# RS3232.net
KiCad netlist of a schematic drawn in Altium Designer
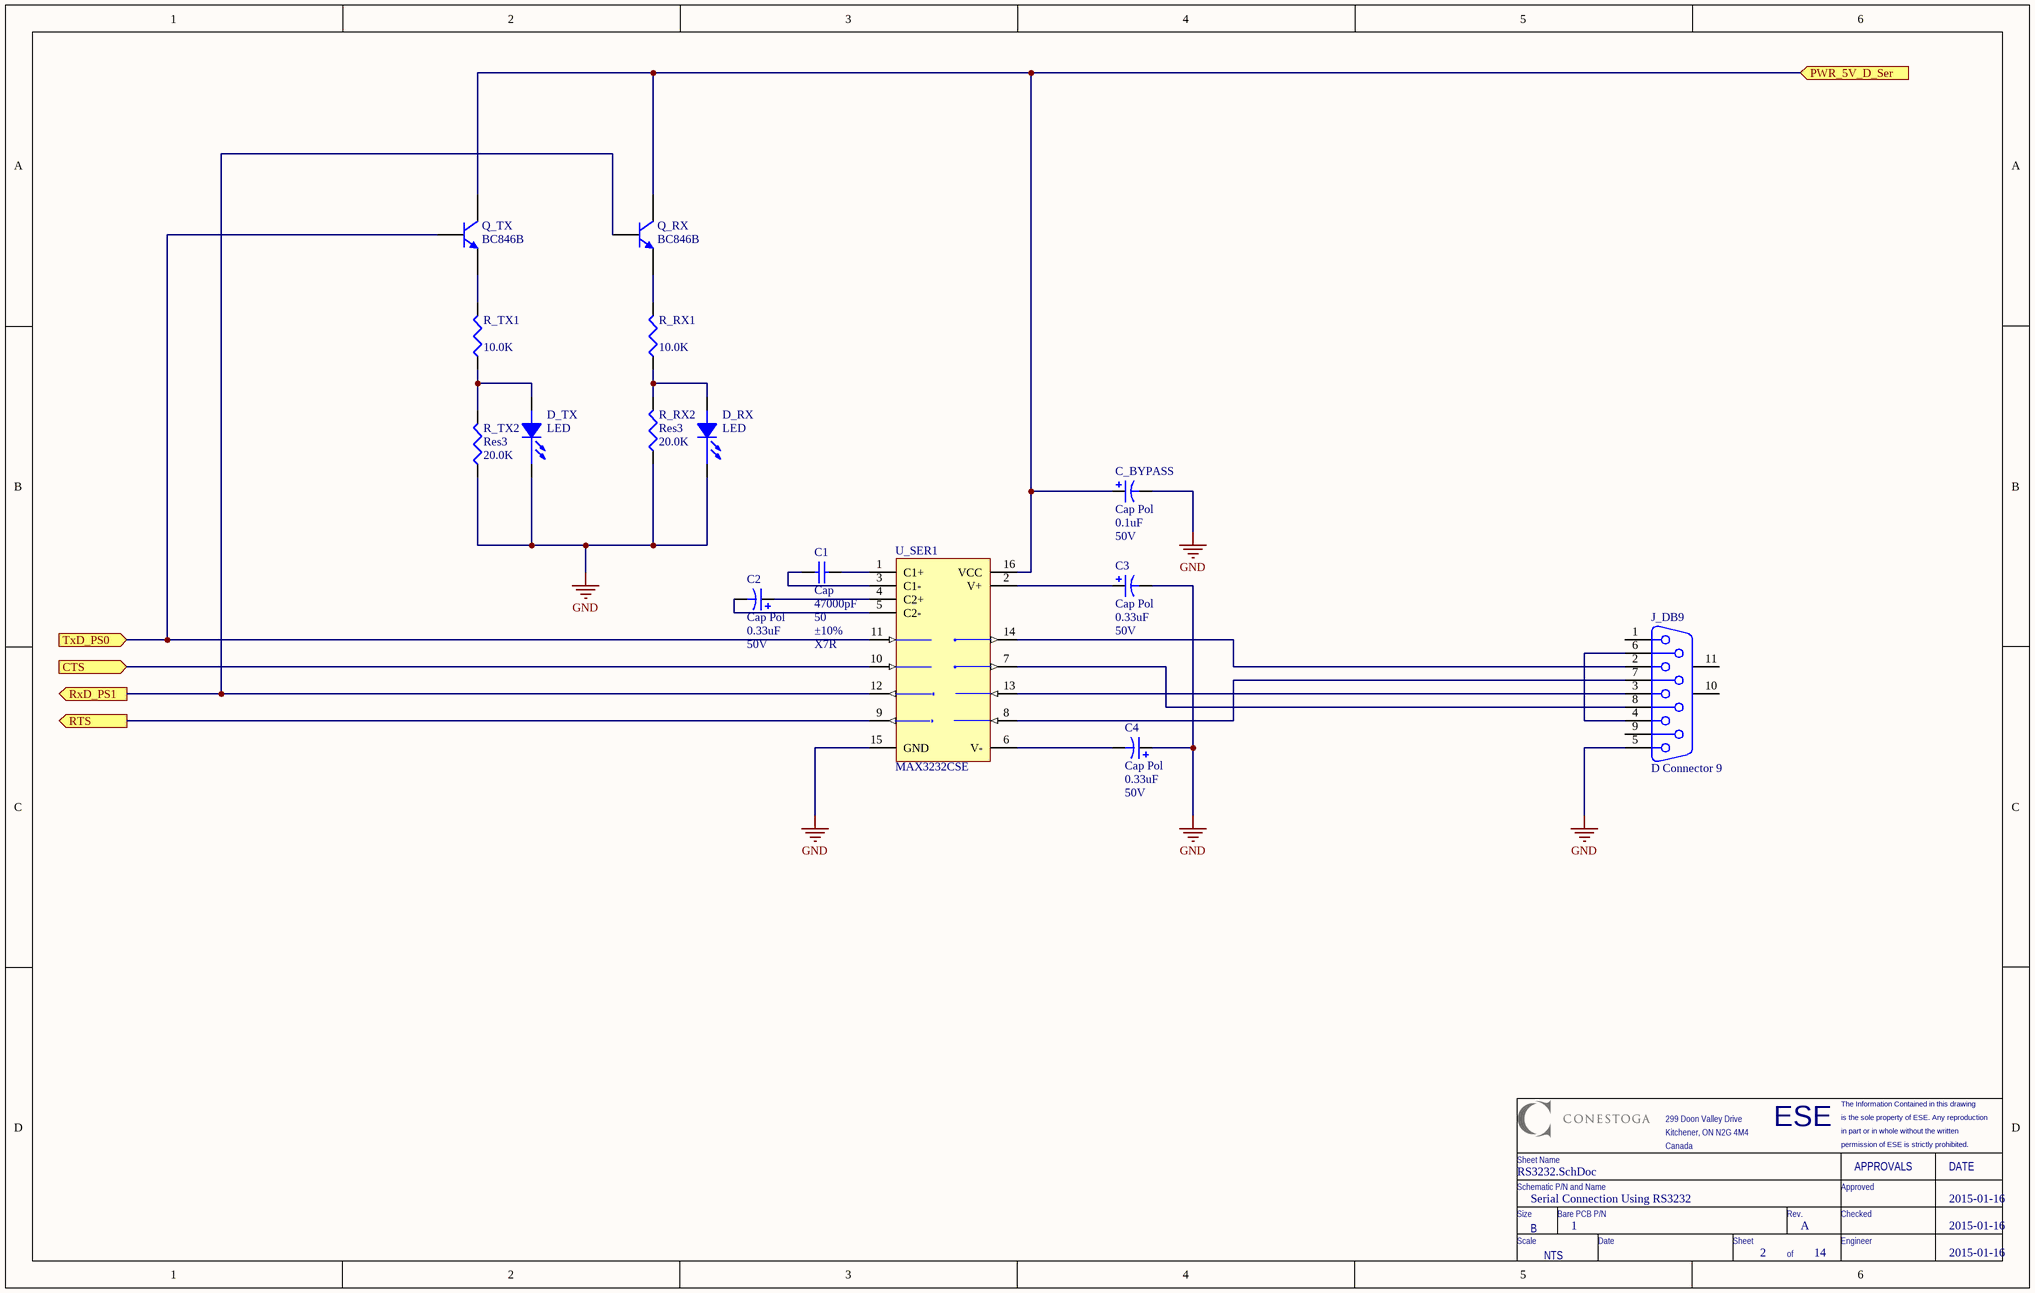
[diagram p0: RS3232.SchDoc]

(export (version "E")
  (design (tool "Eeschema 10.0.6"))
  (components
    (comp (ref "C1")
      (value "Cap")
      (footprint "CAPC2012X09M")
      (description "CAP CER 47000pF 50v X7R 0805")
      (fields
        (field (name "ALTIUM_VALUE") "47000pF")
        (field (name "WV") "50")
        (field (name "TOLERANCE") "±10%")
        (field (name "TYPE") "X7R")
        (field (name "MPN") "C0805C473K5RACTU")
      )
      (libsource (lib "esd_library") (part "CAP-X7R-47000pF-50V-±10%"))
    )
    (comp (ref "C2")
      (value "Cap Pol")
      (footprint "CAPACITOR_3MM")
      (description "CAP 85C 0.33uF ±20% 50V WX Series Aluminum Electrolytic")
      (fields
        (field (name "MPN") "UWX1HR33MCL2GB")
        (field (name "ALTIUM_VALUE") "0.33uF")
        (field (name "VOLTAGE") "50V")
      )
      (libsource (lib "esd_library") (part "Cap Polar-0.33uF-50V"))
    )
    (comp (ref "C3")
      (value "Cap Pol")
      (footprint "CAPACITOR_3MM")
      (description "CAP 85C 0.33uF ±20% 50V WX Series Aluminum Electrolytic")
      (fields
        (field (name "MPN") "UWX1HR33MCL2GB")
        (field (name "ALTIUM_VALUE") "0.33uF")
        (field (name "VOLTAGE") "50V")
      )
      (libsource (lib "esd_library") (part "Cap Polar-0.33uF-50V"))
    )
    (comp (ref "C4")
      (value "Cap Pol")
      (footprint "CAPACITOR_3MM")
      (description "CAP 85C 0.33uF ±20% 50V WX Series Aluminum Electrolytic")
      (fields
        (field (name "MPN") "UWX1HR33MCL2GB")
        (field (name "ALTIUM_VALUE") "0.33uF")
        (field (name "VOLTAGE") "50V")
      )
      (libsource (lib "esd_library") (part "Cap Polar-0.33uF-50V"))
    )
    (comp (ref "C_BYPASS")
      (value "Cap Pol")
      (footprint "CAPACITOR_3MM")
      (description "CAP 85C 0.1uF ±20% 50V WX Series Aluminum Electrolytic")
      (fields
        (field (name "MPN") "UWX1H0R1MCL2GB")
        (field (name "ALTIUM_VALUE") "0.1uF")
        (field (name "VOLTAGE") "50V")
      )
      (libsource (lib "esd_library") (part "Cap Polar-0.1uF-50V"))
    )
    (comp (ref "D_RX") (value "LED") (footprint "0603") (libsource (lib "esd_library") (part "LED")))
    (comp (ref "D_TX") (value "LED") (footprint "0603") (libsource (lib "esd_library") (part "LED")))
    (comp (ref "J_DB9")
      (value "D Connector 9")
      (footprint "DSUB1.385-2H9")
      (description "Receptacle Assembly, 9 Position, Right Angle")
      (fields (field (name "MPN") "ADF09A-KG-TASB3-R"))
      (libsource (lib "esd_library") (part "D Connector 9"))
    )
    (comp (ref "Q_RX")
      (value "BC846B")
      (footprint "SOT95P230X110-3M")
      (description "NPN General Purpose Amplifier")
      (libsource (lib "esd_library") (part "BC846B"))
    )
    (comp (ref "Q_TX")
      (value "BC846B")
      (footprint "SOT95P230X110-3M")
      (description "NPN General Purpose Amplifier")
      (libsource (lib "esd_library") (part "BC846B"))
    )
    (comp (ref "R_RX1")
      (value "10.0K")
      (footprint "RESC2112X05M")
      (description "RES SMD 10.0K OHM 1% 1/8W 0805")
      (fields (field (name "MPN") "CRCW080510K0FKEA") (field (name "Comment") "Res3"))
      (libsource (lib "esd_library") (part "Resistor_10.0K"))
    )
    (comp (ref "R_RX2")
      (value "Res3")
      (footprint "RESC2112X05M")
      (description "RES SMD 20.0K OHM 1% 1/8W 0805")
      (fields (field (name "ALTIUM_VALUE") "20.0K") (field (name "MPN") "CRCW080520K0FKEA"))
      (libsource (lib "esd_library") (part "Resistor_20.0K"))
    )
    (comp (ref "R_TX1")
      (value "10.0K")
      (footprint "RESC2112X05M")
      (description "RES SMD 10.0K OHM 1% 1/8W 0805")
      (fields (field (name "MPN") "CRCW080510K0FKEA") (field (name "Comment") "Res3"))
      (libsource (lib "esd_library") (part "Resistor_10.0K"))
    )
    (comp (ref "R_TX2")
      (value "Res3")
      (footprint "RESC2112X05M")
      (description "RES SMD 20.0K OHM 1% 1/8W 0805")
      (fields (field (name "ALTIUM_VALUE") "20.0K") (field (name "MPN") "CRCW080520K0FKEA"))
      (libsource (lib "esd_library") (part "Resistor_20.0K"))
    )
    (comp (ref "U_SER1")
      (value "MAX3232CSE")
      (footprint "NSO16_N")
      (description "3.0V TO 5.5V, Low-Power, up to 1Mbps, True RS-232 Transceiver Using Four 0.1µF External Capacitor")
      (fields (field (name "MPN") "MAX3232CSE+") (field (name "PUBLISHER") "Altium Limited"))
      (libsource (lib "esd_library") (part "MAX3232CSE"))
    )
  )
  (nets
    (net (code "1") (name "/CTS") (class "Default")
      (node (ref "U_SER1") (pin "10") (pinfunction "T2IN_10") (pintype "input"))
    )
    (net (code "2") (name "/PWR_5V_D_Ser") (class "Default")
      (node (ref "C_BYPASS") (pin "1") (pinfunction "1_1") (pintype "passive"))
      (node (ref "Q_RX") (pin "3") (pinfunction "C_3") (pintype "passive"))
      (node (ref "Q_TX") (pin "3") (pinfunction "C_3") (pintype "passive"))
      (node (ref "U_SER1") (pin "16") (pinfunction "VCC_16") (pintype "power_in"))
    )
    (net (code "3") (name "/RTS") (class "Default")
      (node (ref "U_SER1") (pin "9") (pinfunction "R2OUT_9") (pintype "output"))
    )
    (net (code "4") (name "/RxD_PS1") (class "Default")
      (node (ref "Q_RX") (pin "1") (pinfunction "B_1") (pintype "passive"))
      (node (ref "U_SER1") (pin "12") (pinfunction "R1OUT_12") (pintype "output"))
    )
    (net (code "5") (name "/TxD_PS0") (class "Default")
      (node (ref "Q_TX") (pin "1") (pinfunction "B_1") (pintype "passive"))
      (node (ref "U_SER1") (pin "11") (pinfunction "T1IN_11") (pintype "input"))
    )
    (net (code "6") (name "GND") (class "Default")
      (node (ref "C3") (pin "2") (pinfunction "2_2") (pintype "passive"))
      (node (ref "C4") (pin "1") (pinfunction "1_1") (pintype "passive"))
      (node (ref "C_BYPASS") (pin "2") (pinfunction "2_2") (pintype "passive"))
      (node (ref "D_RX") (pin "2") (pinfunction "C_2") (pintype "passive"))
      (node (ref "D_TX") (pin "2") (pinfunction "C_2") (pintype "passive"))
      (node (ref "J_DB9") (pin "5") (pinfunction "5_5") (pintype "passive"))
      (node (ref "R_RX2") (pin "1") (pinfunction "1_1") (pintype "passive"))
      (node (ref "R_TX2") (pin "1") (pinfunction "1_1") (pintype "passive"))
      (node (ref "U_SER1") (pin "15") (pinfunction "GND_15") (pintype "power_in"))
    )
    (net (code "7") (name "Net-(D_RX-A)") (class "Default")
      (node (ref "D_RX") (pin "1") (pinfunction "A_1") (pintype "passive"))
      (node (ref "R_RX1") (pin "1") (pinfunction "1_1") (pintype "passive"))
      (node (ref "R_RX2") (pin "2") (pinfunction "2_2") (pintype "passive"))
    )
    (net (code "8") (name "Net-(D_TX-A)") (class "Default")
      (node (ref "D_TX") (pin "1") (pinfunction "A_1") (pintype "passive"))
      (node (ref "R_TX1") (pin "1") (pinfunction "1_1") (pintype "passive"))
      (node (ref "R_TX2") (pin "2") (pinfunction "2_2") (pintype "passive"))
    )
    (net (code "9") (name "Net-(J_DB9-Pad4)") (class "Default")
      (node (ref "J_DB9") (pin "4") (pinfunction "4_4") (pintype "passive"))
      (node (ref "J_DB9") (pin "6") (pinfunction "6_6") (pintype "passive"))
    )
    (net (code "10") (name "Net-(Q_RX-E)") (class "Default")
      (node (ref "Q_RX") (pin "2") (pinfunction "E_2") (pintype "passive"))
      (node (ref "R_RX1") (pin "2") (pinfunction "2_2") (pintype "passive"))
    )
    (net (code "11") (name "Net-(Q_TX-E)") (class "Default")
      (node (ref "Q_TX") (pin "2") (pinfunction "E_2") (pintype "passive"))
      (node (ref "R_TX1") (pin "2") (pinfunction "2_2") (pintype "passive"))
    )
    (net (code "12") (name "Net-(U_SER1-C1+)") (class "Default")
      (node (ref "C1") (pin "2") (pinfunction "2_2") (pintype "passive"))
      (node (ref "U_SER1") (pin "1") (pinfunction "C1+_1") (pintype "passive"))
    )
    (net (code "13") (name "Net-(U_SER1-C1-)") (class "Default")
      (node (ref "C1") (pin "1") (pinfunction "1_1") (pintype "passive"))
      (node (ref "U_SER1") (pin "3") (pinfunction "C1-_3") (pintype "passive"))
    )
    (net (code "14") (name "Net-(U_SER1-C2+)") (class "Default")
      (node (ref "C2") (pin "1") (pinfunction "1_1") (pintype "passive"))
      (node (ref "U_SER1") (pin "4") (pinfunction "C2+_4") (pintype "passive"))
    )
    (net (code "15") (name "Net-(U_SER1-C2-)") (class "Default")
      (node (ref "C2") (pin "2") (pinfunction "2_2") (pintype "passive"))
      (node (ref "U_SER1") (pin "5") (pinfunction "C2-_5") (pintype "passive"))
    )
    (net (code "16") (name "Net-(U_SER1-R1IN)") (class "Default")
      (node (ref "J_DB9") (pin "3") (pinfunction "3_3") (pintype "passive"))
      (node (ref "U_SER1") (pin "13") (pinfunction "R1IN_13") (pintype "input"))
    )
    (net (code "17") (name "Net-(U_SER1-R2IN)") (class "Default")
      (node (ref "J_DB9") (pin "7") (pinfunction "7_7") (pintype "passive"))
      (node (ref "U_SER1") (pin "8") (pinfunction "R2IN_8") (pintype "input"))
    )
    (net (code "18") (name "Net-(U_SER1-T1OUT)") (class "Default")
      (node (ref "J_DB9") (pin "2") (pinfunction "2_2") (pintype "passive"))
      (node (ref "U_SER1") (pin "14") (pinfunction "T1OUT_14") (pintype "output"))
    )
    (net (code "19") (name "Net-(U_SER1-T2OUT)") (class "Default")
      (node (ref "J_DB9") (pin "8") (pinfunction "8_8") (pintype "passive"))
      (node (ref "U_SER1") (pin "7") (pinfunction "T2OUT_7") (pintype "output"))
    )
    (net (code "20") (name "Net-(U_SER1-V+)") (class "Default")
      (node (ref "C3") (pin "1") (pinfunction "1_1") (pintype "passive"))
      (node (ref "U_SER1") (pin "2") (pinfunction "V+_2") (pintype "power_in"))
    )
    (net (code "21") (name "Net-(U_SER1-V-)") (class "Default")
      (node (ref "C4") (pin "2") (pinfunction "2_2") (pintype "passive"))
      (node (ref "U_SER1") (pin "6") (pinfunction "V-_6") (pintype "power_in"))
    )
    (net (code "22") (name "unconnected-(J_DB9-MH1-Pad10)") (class "Default")
      (node (ref "J_DB9") (pin "10") (pinfunction "MH1_10") (pintype "passive"))
    )
    (net (code "23") (name "unconnected-(J_DB9-MH2-Pad11)") (class "Default")
      (node (ref "J_DB9") (pin "11") (pinfunction "MH2_11") (pintype "passive"))
    )
    (net (code "24") (name "unconnected-(J_DB9-Pad1)") (class "Default")
      (node (ref "J_DB9") (pin "1") (pinfunction "1_1") (pintype "passive"))
    )
    (net (code "25") (name "unconnected-(J_DB9-Pad9)") (class "Default")
      (node (ref "J_DB9") (pin "9") (pinfunction "9_9") (pintype "passive"))
    )
  )
)
